# ee40.net
KiCad netlist of a schematic drawn in EAGLE
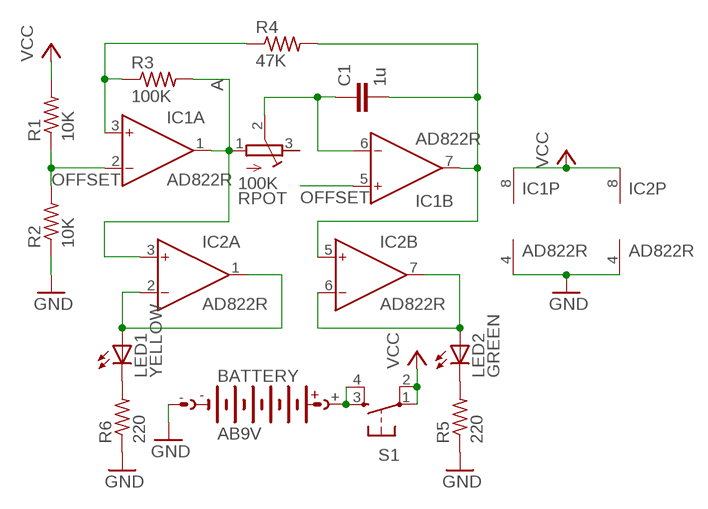
[diagram p0: schematic, sheet 1]

(export (version "E")
  (design (tool "Eeschema 10.0.6"))
  (components
    (comp (ref "BATTERY")
      (value "AB9V")
      (footprint "eagle-import:AB9V")
      (libsource (lib "eagle-import") (part "AB9V"))
    )
    (comp (ref "C1")
      (value "1u")
      (footprint "eagle-import:0805")
      (libsource (lib "eagle-import") (part "CAP0805"))
    )
    (comp (ref "IC1")
      (value "AD822R")
      (footprint "eagle-import:SO8")
      (fields (field (name "MF") "ANALOG DEVICES") (field (name "MPN") "AD822BRZ"))
      (libsource (lib "eagle-import") (part "AD822R"))
    )
    (comp (ref "IC2")
      (value "AD822R")
      (footprint "eagle-import:SO8")
      (fields (field (name "MF") "ANALOG DEVICES") (field (name "MPN") "AD822BRZ"))
      (libsource (lib "eagle-import") (part "AD822R"))
    )
    (comp (ref "LED1")
      (value "YELLOW")
      (footprint "eagle-import:LED3MM")
      (libsource (lib "eagle-import") (part "LED3MM"))
    )
    (comp (ref "LED2")
      (value "GREEN")
      (footprint "eagle-import:LED3MM")
      (libsource (lib "eagle-import") (part "LED3MM"))
    )
    (comp (ref "R1")
      (value "10K")
      (footprint "eagle-import:R0603")
      (libsource (lib "eagle-import") (part "R-US_R0603"))
    )
    (comp (ref "R2")
      (value "10K")
      (footprint "eagle-import:R0603")
      (libsource (lib "eagle-import") (part "R-US_R0603"))
    )
    (comp (ref "R3")
      (value "100K")
      (footprint "eagle-import:R0603")
      (libsource (lib "eagle-import") (part "R-US_R0603"))
    )
    (comp (ref "R4")
      (value "47K")
      (footprint "eagle-import:R0603")
      (libsource (lib "eagle-import") (part "R-US_R0603"))
    )
    (comp (ref "R5")
      (value "220")
      (footprint "eagle-import:R0603")
      (libsource (lib "eagle-import") (part "R-US_R0603"))
    )
    (comp (ref "R6")
      (value "220")
      (footprint "eagle-import:R0603")
      (libsource (lib "eagle-import") (part "R-US_R0603"))
    )
    (comp (ref "RPOT")
      (value "100K")
      (footprint "eagle-import:RTRIM5X")
      (libsource (lib "eagle-import") (part "R-TRIMM5X"))
    )
    (comp (ref "S1")
      (value "TAC_SWITCHPTH")
      (footprint "eagle-import:TACTILE-PTH")
      (libsource (lib "eagle-import") (part "TAC_SWITCHPTH"))
    )
  )
  (nets
    (net (code "1") (name "/A") (class "Default")
      (node (ref "IC1") (pin "1") (pinfunction "OUT_1") (pintype "output"))
      (node (ref "IC2") (pin "3") (pinfunction "IN+_3") (pintype "input"))
      (node (ref "R3") (pin "2") (pinfunction "2_2") (pintype "passive"))
      (node (ref "RPOT") (pin "1") (pinfunction "E_1") (pintype "passive"))
    )
    (net (code "2") (name "/OFFSET") (class "Default")
      (node (ref "IC1") (pin "2") (pinfunction "IN-_2") (pintype "input"))
      (node (ref "IC1") (pin "5") (pinfunction "IN+_5") (pintype "input"))
      (node (ref "R1") (pin "1") (pinfunction "1_1") (pintype "passive"))
      (node (ref "R2") (pin "2") (pinfunction "2_2") (pintype "passive"))
    )
    (net (code "3") (name "GND") (class "Default")
      (node (ref "BATTERY") (pin "-") (pinfunction "-_-") (pintype "passive"))
      (node (ref "IC1") (pin "4") (pinfunction "V-_4") (pintype "power_in"))
      (node (ref "IC2") (pin "4") (pinfunction "V-_4") (pintype "power_in"))
      (node (ref "R2") (pin "1") (pinfunction "1_1") (pintype "passive"))
      (node (ref "R5") (pin "1") (pinfunction "1_1") (pintype "passive"))
      (node (ref "R6") (pin "1") (pinfunction "1_1") (pintype "passive"))
    )
    (net (code "4") (name "Net-(BATTERY-Pad+)") (class "Default")
      (node (ref "BATTERY") (pin "+") (pinfunction "+_+") (pintype "passive"))
      (node (ref "S1") (pin "3") (pinfunction "3_3") (pintype "passive"))
      (node (ref "S1") (pin "4") (pinfunction "4_4") (pintype "passive"))
    )
    (net (code "5") (name "Net-(IC1A-IN+)") (class "Default")
      (node (ref "IC1") (pin "3") (pinfunction "IN+_3") (pintype "input"))
      (node (ref "R3") (pin "1") (pinfunction "1_1") (pintype "passive"))
      (node (ref "R4") (pin "1") (pinfunction "1_1") (pintype "passive"))
    )
    (net (code "6") (name "Net-(IC1B-IN-)") (class "Default")
      (node (ref "C1") (pin "1") (pinfunction "1_1") (pintype "passive"))
      (node (ref "IC1") (pin "6") (pinfunction "IN-_6") (pintype "input"))
      (node (ref "RPOT") (pin "2") (pinfunction "S_2") (pintype "passive"))
    )
    (net (code "7") (name "Net-(IC1B-OUT)") (class "Default")
      (node (ref "C1") (pin "2") (pinfunction "2_2") (pintype "passive"))
      (node (ref "IC1") (pin "7") (pinfunction "OUT_7") (pintype "output"))
      (node (ref "IC2") (pin "5") (pinfunction "IN+_5") (pintype "input"))
      (node (ref "R4") (pin "2") (pinfunction "2_2") (pintype "passive"))
    )
    (net (code "8") (name "Net-(IC2A-IN-)") (class "Default")
      (node (ref "IC2") (pin "1") (pinfunction "OUT_1") (pintype "output"))
      (node (ref "IC2") (pin "2") (pinfunction "IN-_2") (pintype "input"))
      (node (ref "LED1") (pin "A") (pinfunction "A_A") (pintype "passive"))
    )
    (net (code "9") (name "Net-(IC2B-IN-)") (class "Default")
      (node (ref "IC2") (pin "6") (pinfunction "IN-_6") (pintype "input"))
      (node (ref "IC2") (pin "7") (pinfunction "OUT_7") (pintype "output"))
      (node (ref "LED2") (pin "A") (pinfunction "A_A") (pintype "passive"))
    )
    (net (code "10") (name "Net-(LED1-C)") (class "Default")
      (node (ref "LED1") (pin "K") (pinfunction "C_K") (pintype "passive"))
      (node (ref "R6") (pin "2") (pinfunction "2_2") (pintype "passive"))
    )
    (net (code "11") (name "Net-(LED2-C)") (class "Default")
      (node (ref "LED2") (pin "K") (pinfunction "C_K") (pintype "passive"))
      (node (ref "R5") (pin "2") (pinfunction "2_2") (pintype "passive"))
    )
    (net (code "12") (name "VCC") (class "Default")
      (node (ref "IC1") (pin "8") (pinfunction "V+_8") (pintype "power_in"))
      (node (ref "IC2") (pin "8") (pinfunction "V+_8") (pintype "power_in"))
      (node (ref "R1") (pin "2") (pinfunction "2_2") (pintype "passive"))
      (node (ref "S1") (pin "1") (pinfunction "1_1") (pintype "passive"))
      (node (ref "S1") (pin "2") (pinfunction "2_2") (pintype "passive"))
    )
    (net (code "13") (name "unconnected-(RPOT-A-Pad3)") (class "Default")
      (node (ref "RPOT") (pin "3") (pinfunction "A_3") (pintype "passive"))
    )
  )
)
